# Connectors.net
KiCad netlist of a schematic drawn in Altium Designer
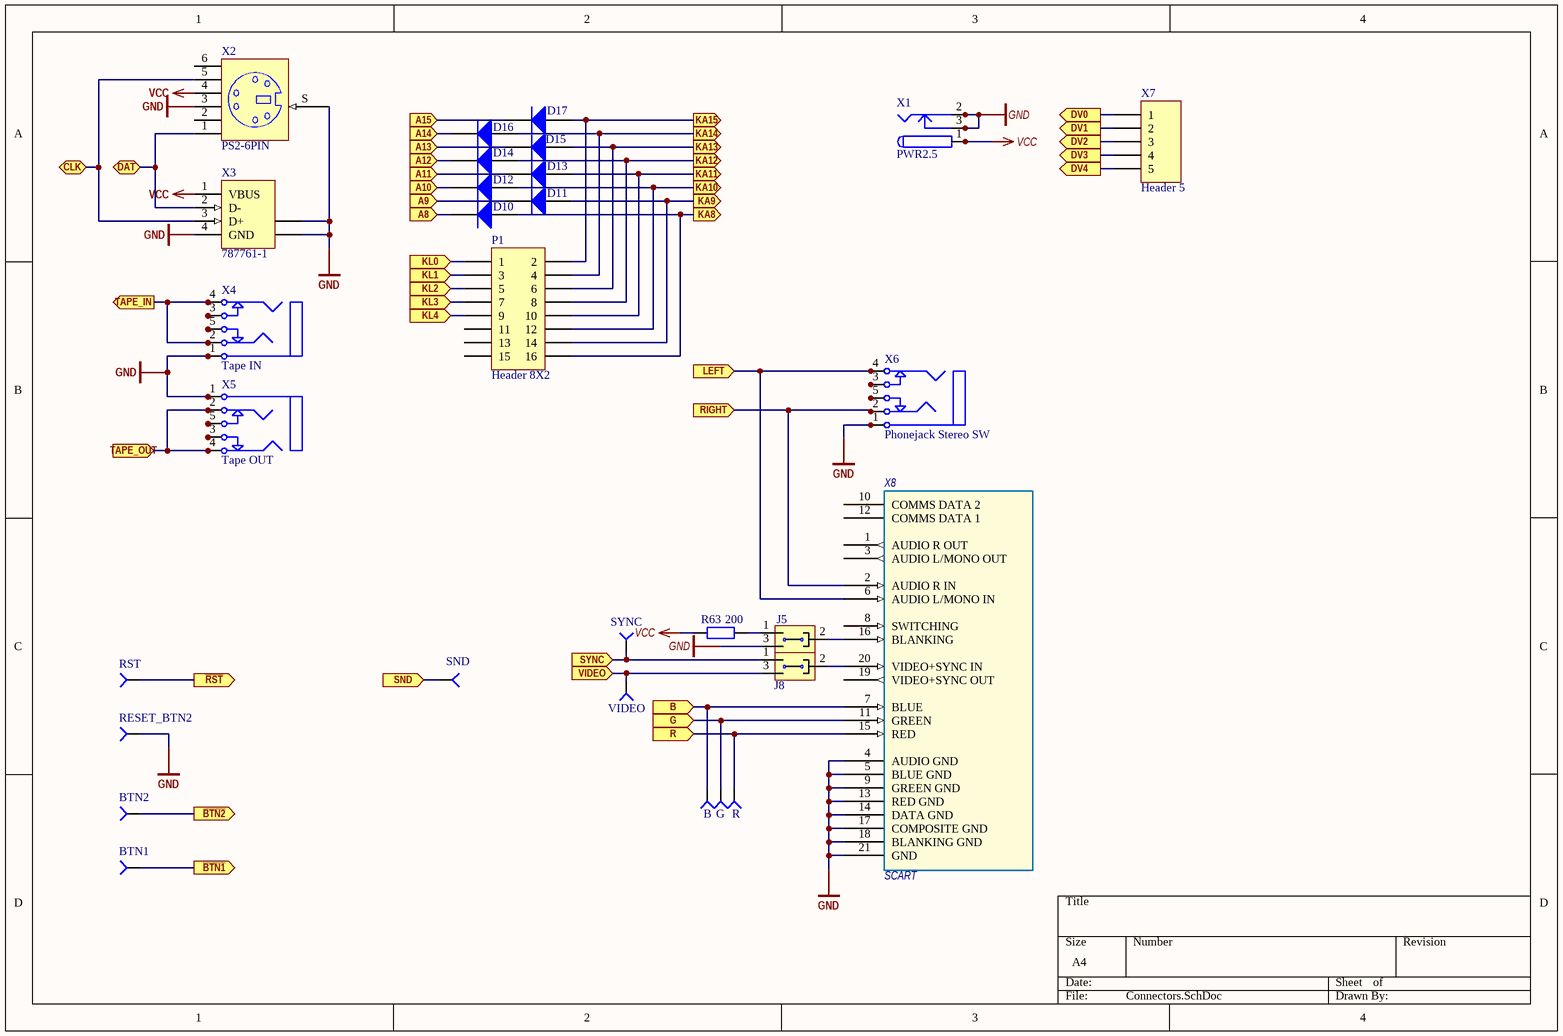
[diagram p0: Connectors.SchDoc]

(export (version "E")
  (design (tool "Eeschema 10.0.6"))
  (components
    (comp (ref "B")
      (value "~")
      (footprint "PIN1")
      (description "Socket")
      (fields (field (name "PUBLISHER") "Altium Limited"))
      (libsource (lib "Lenin") (part "Socket"))
    )
    (comp (ref "BTN1")
      (value "Socket")
      (footprint "PIN1")
      (fields (field (name "PUBLISHER") "Altium Limited"))
      (libsource (lib "Lenin") (part "Socket"))
    )
    (comp (ref "BTN2")
      (value "Socket")
      (footprint "PIN1")
      (fields (field (name "PUBLISHER") "Altium Limited"))
      (libsource (lib "Lenin") (part "Socket"))
    )
    (comp (ref "D10")
      (value "Diode 1N4148")
      (footprint "DO-35")
      (description "High Conductance Fast Diode")
      (fields (field (name "PUBLISHER") "Altium Limited"))
      (libsource (lib "Miscellaneous Devices") (part "Diode 1N4148"))
    )
    (comp (ref "D11")
      (value "Diode 1N4148")
      (footprint "DO-35")
      (description "High Conductance Fast Diode")
      (fields (field (name "PUBLISHER") "Altium Limited"))
      (libsource (lib "Miscellaneous Devices") (part "Diode 1N4148"))
    )
    (comp (ref "D12")
      (value "Diode 1N4148")
      (footprint "DO-35")
      (description "High Conductance Fast Diode")
      (fields (field (name "PUBLISHER") "Altium Limited"))
      (libsource (lib "Miscellaneous Devices") (part "Diode 1N4148"))
    )
    (comp (ref "D13")
      (value "Diode 1N4148")
      (footprint "DO-35")
      (description "High Conductance Fast Diode")
      (fields (field (name "PUBLISHER") "Altium Limited"))
      (libsource (lib "Miscellaneous Devices") (part "Diode 1N4148"))
    )
    (comp (ref "D14")
      (value "Diode 1N4148")
      (footprint "DO-35")
      (description "High Conductance Fast Diode")
      (fields (field (name "PUBLISHER") "Altium Limited"))
      (libsource (lib "Miscellaneous Devices") (part "Diode 1N4148"))
    )
    (comp (ref "D15")
      (value "Diode 1N4148")
      (footprint "DO-35")
      (description "High Conductance Fast Diode")
      (fields (field (name "PUBLISHER") "Altium Limited"))
      (libsource (lib "Miscellaneous Devices") (part "Diode 1N4148"))
    )
    (comp (ref "D16")
      (value "Diode 1N4148")
      (footprint "DO-35")
      (description "High Conductance Fast Diode")
      (fields (field (name "PUBLISHER") "Altium Limited"))
      (libsource (lib "Miscellaneous Devices") (part "Diode 1N4148"))
    )
    (comp (ref "D17")
      (value "Diode 1N4148")
      (footprint "DO-35")
      (description "High Conductance Fast Diode")
      (fields (field (name "PUBLISHER") "Altium Limited"))
      (libsource (lib "Miscellaneous Devices") (part "Diode 1N4148"))
    )
    (comp (ref "G")
      (value "~")
      (footprint "PIN1")
      (description "Socket")
      (fields (field (name "PUBLISHER") "Altium Limited"))
      (libsource (lib "Lenin") (part "Socket"))
    )
    (comp (ref "J5")
      (value "Jump3")
      (footprint "Miscellaneous Connectors:MHDR1X3")
      (libsource (lib "Lenin") (part "Jump3"))
    )
    (comp (ref "J8")
      (value "Jump3")
      (footprint "Miscellaneous Connectors:MHDR1X3")
      (libsource (lib "Lenin") (part "Jump3"))
    )
    (comp (ref "P1")
      (value "Header 8X2")
      (footprint "HDR2X8")
      (description "Header, 8-Pin, Dual row")
      (fields (field (name "PUBLISHER") "Altium Limited"))
      (libsource (lib "Miscellaneous Connectors") (part "Header 8X2"))
    )
    (comp (ref "R")
      (value "~")
      (footprint "PIN1")
      (description "Socket")
      (fields (field (name "PUBLISHER") "Altium Limited"))
      (libsource (lib "Lenin") (part "Socket"))
    )
    (comp (ref "R63")
      (value "200")
      (footprint "Lenin:AXIAL-0.4")
      (description "Resistor")
      (fields (field (name "Comment") "Res2") (field (name "PUBLISHER") "Altium Limited"))
      (libsource (lib "Lenin") (part "Res2"))
    )
    (comp (ref "RESET_BTN2")
      (value "~")
      (footprint "PIN1")
      (description "Socket")
      (fields (field (name "PUBLISHER") "Altium Limited"))
      (libsource (lib "Lenin") (part "Socket"))
    )
    (comp (ref "RST")
      (value "~")
      (footprint "PIN1")
      (description "Socket")
      (fields (field (name "PUBLISHER") "Altium Limited"))
      (libsource (lib "Lenin") (part "Socket"))
    )
    (comp (ref "SND")
      (value "~")
      (footprint "PIN1")
      (description "Socket")
      (fields (field (name "PUBLISHER") "Altium Limited"))
      (libsource (lib "Lenin") (part "Socket"))
    )
    (comp (ref "SYNC")
      (value "~")
      (footprint "PIN1")
      (description "Socket")
      (fields (field (name "PUBLISHER") "Altium Limited"))
      (libsource (lib "Lenin") (part "Socket"))
    )
    (comp (ref "VIDEO")
      (value "~")
      (footprint "PIN1")
      (description "Socket")
      (fields (field (name "PUBLISHER") "Altium Limited"))
      (libsource (lib "Lenin") (part "Socket"))
    )
    (comp (ref "X1")
      (value "PWR2.5")
      (footprint "KLD-0202")
      (description "Low Voltage Power Supply Connector")
      (fields (field (name "PUBLISHER") "Altium Limited"))
      (libsource (lib "Miscellaneous Connectors") (part "PWR2.5"))
    )
    (comp (ref "X2")
      (value "PS2-6PIN")
      (footprint "PS2-6PIN")
      (description "6 Pin Through Hole PS2 Socket (Kycon P/N)")
      (fields (field (name "PUBLISHER") "Altium Limited"))
      (libsource (lib "Miscellaneous Connectors") (part "PS2-6PIN"))
    )
    (comp (ref "X3")
      (value "787761-1")
      (footprint "787761")
      (description "USB 1.1, Right Angle, Thru-Hole, A Type, Receptacle, 4 Position, Black")
      (fields (field (name "PUBLISHER") "Altium Limited"))
      (libsource (lib "AMP Serial Bus USB") (part "787761-1"))
    )
    (comp (ref "X4")
      (value "Tape IN")
      (footprint "ST-3150-5N")
      (description "3-Conductor Jack with 2 break contacts (normals) and 2 auxiliary make contacts")
      (fields (field (name "PUBLISHER") "Altium Limited"))
      (libsource (lib "Miscellaneous Connectors") (part "Phonejack Stereo SW"))
    )
    (comp (ref "X5")
      (value "Tape OUT")
      (footprint "ST-3150-5N")
      (description "3-Conductor Jack with 2 break contacts (normals) and 2 auxiliary make contacts")
      (fields (field (name "PUBLISHER") "Altium Limited"))
      (libsource (lib "Miscellaneous Connectors") (part "Phonejack Stereo SW"))
    )
    (comp (ref "X6")
      (value "Phonejack Stereo SW")
      (footprint "ST-3150-5N")
      (description "3-Conductor Jack with 2 break contacts (normals) and 2 auxiliary make contacts")
      (fields (field (name "PUBLISHER") "Altium Limited"))
      (libsource (lib "Miscellaneous Connectors") (part "Phonejack Stereo SW"))
    )
    (comp (ref "X7")
      (value "Header 5")
      (footprint "HDR1X5")
      (description "Header, 5-Pin")
      (fields (field (name "PUBLISHER") "Altium Limited"))
      (libsource (lib "Miscellaneous Connectors") (part "Header 5"))
    )
    (comp (ref "X8") (value "SCART") (footprint "Lenin:SCART") (libsource (lib "Lenin") (part "SCART")))
  )
  (nets
    (net (code "1") (name "/A8") (class "Default")
      (node (ref "D10") (pin "2") (pinfunction "K_2") (pintype "passive"))
    )
    (net (code "2") (name "/A9") (class "Default")
      (node (ref "D11") (pin "2") (pinfunction "K_2") (pintype "passive"))
    )
    (net (code "3") (name "/A10") (class "Default")
      (node (ref "D12") (pin "2") (pinfunction "K_2") (pintype "passive"))
    )
    (net (code "4") (name "/A11") (class "Default")
      (node (ref "D13") (pin "2") (pinfunction "K_2") (pintype "passive"))
    )
    (net (code "5") (name "/A12") (class "Default")
      (node (ref "D14") (pin "2") (pinfunction "K_2") (pintype "passive"))
    )
    (net (code "6") (name "/A13") (class "Default")
      (node (ref "D15") (pin "2") (pinfunction "K_2") (pintype "passive"))
    )
    (net (code "7") (name "/A14") (class "Default")
      (node (ref "D16") (pin "2") (pinfunction "K_2") (pintype "passive"))
    )
    (net (code "8") (name "/A15") (class "Default")
      (node (ref "D17") (pin "2") (pinfunction "K_2") (pintype "passive"))
    )
    (net (code "9") (name "/B") (class "Default")
      (node (ref "B") (pin "1") (pinfunction "1_1") (pintype "passive"))
      (node (ref "X8") (pin "7") (pinfunction "BLUE_7") (pintype "input"))
    )
    (net (code "10") (name "/CLK") (class "Default")
      (node (ref "X2") (pin "5") (pinfunction "5_5") (pintype "passive"))
      (node (ref "X3") (pin "3") (pinfunction "D+_3") (pintype "input"))
    )
    (net (code "11") (name "/DAT") (class "Default")
      (node (ref "X2") (pin "1") (pinfunction "1_1") (pintype "passive"))
      (node (ref "X3") (pin "2") (pinfunction "D-_2") (pintype "input"))
    )
    (net (code "12") (name "/DV0") (class "Default")
      (node (ref "X7") (pin "1") (pinfunction "1_1") (pintype "passive"))
    )
    (net (code "13") (name "/DV1") (class "Default")
      (node (ref "X7") (pin "2") (pinfunction "2_2") (pintype "passive"))
    )
    (net (code "14") (name "/DV2") (class "Default")
      (node (ref "X7") (pin "3") (pinfunction "3_3") (pintype "passive"))
    )
    (net (code "15") (name "/DV3") (class "Default")
      (node (ref "X7") (pin "4") (pinfunction "4_4") (pintype "passive"))
    )
    (net (code "16") (name "/DV4") (class "Default")
      (node (ref "X7") (pin "5") (pinfunction "5_5") (pintype "passive"))
    )
    (net (code "17") (name "/G") (class "Default")
      (node (ref "G") (pin "1") (pinfunction "1_1") (pintype "passive"))
      (node (ref "X8") (pin "11") (pinfunction "GREEN_11") (pintype "input"))
    )
    (net (code "18") (name "/KA8") (class "Default")
      (node (ref "D10") (pin "1") (pinfunction "A_1") (pintype "passive"))
      (node (ref "P1") (pin "16") (pinfunction "16_16") (pintype "passive"))
    )
    (net (code "19") (name "/KA9") (class "Default")
      (node (ref "D11") (pin "1") (pinfunction "A_1") (pintype "passive"))
      (node (ref "P1") (pin "14") (pinfunction "14_14") (pintype "passive"))
    )
    (net (code "20") (name "/KA10") (class "Default")
      (node (ref "D12") (pin "1") (pinfunction "A_1") (pintype "passive"))
      (node (ref "P1") (pin "12") (pinfunction "12_12") (pintype "passive"))
    )
    (net (code "21") (name "/KA11") (class "Default")
      (node (ref "D13") (pin "1") (pinfunction "A_1") (pintype "passive"))
      (node (ref "P1") (pin "10") (pinfunction "10_10") (pintype "passive"))
    )
    (net (code "22") (name "/KA12") (class "Default")
      (node (ref "D14") (pin "1") (pinfunction "A_1") (pintype "passive"))
      (node (ref "P1") (pin "8") (pinfunction "8_8") (pintype "passive"))
    )
    (net (code "23") (name "/KA13") (class "Default")
      (node (ref "D15") (pin "1") (pinfunction "A_1") (pintype "passive"))
      (node (ref "P1") (pin "6") (pinfunction "6_6") (pintype "passive"))
    )
    (net (code "24") (name "/KA14") (class "Default")
      (node (ref "D16") (pin "1") (pinfunction "A_1") (pintype "passive"))
      (node (ref "P1") (pin "4") (pinfunction "4_4") (pintype "passive"))
    )
    (net (code "25") (name "/KA15") (class "Default")
      (node (ref "D17") (pin "1") (pinfunction "A_1") (pintype "passive"))
      (node (ref "P1") (pin "2") (pinfunction "2_2") (pintype "passive"))
    )
    (net (code "26") (name "/KL0") (class "Default")
      (node (ref "P1") (pin "1") (pinfunction "1_1") (pintype "passive"))
    )
    (net (code "27") (name "/KL1") (class "Default")
      (node (ref "P1") (pin "3") (pinfunction "3_3") (pintype "passive"))
    )
    (net (code "28") (name "/KL2") (class "Default")
      (node (ref "P1") (pin "5") (pinfunction "5_5") (pintype "passive"))
    )
    (net (code "29") (name "/KL3") (class "Default")
      (node (ref "P1") (pin "7") (pinfunction "7_7") (pintype "passive"))
    )
    (net (code "30") (name "/KL4") (class "Default")
      (node (ref "P1") (pin "9") (pinfunction "9_9") (pintype "passive"))
    )
    (net (code "31") (name "/LEFT") (class "Default")
      (node (ref "X6") (pin "4") (pinfunction "4_4") (pintype "passive"))
      (node (ref "X6") (pin "4A") (pinfunction "4A_4A") (pintype "passive"))
      (node (ref "X6") (pin "4B") (pinfunction "4B_4B") (pintype "passive"))
      (node (ref "X8") (pin "6") (pinfunction "AUDIO_L/MONO_IN_6") (pintype "input"))
    )
    (net (code "32") (name "/R") (class "Default")
      (node (ref "R") (pin "1") (pinfunction "1_1") (pintype "passive"))
      (node (ref "X8") (pin "15") (pinfunction "RED_15") (pintype "input"))
    )
    (net (code "33") (name "/RIGHT") (class "Default")
      (node (ref "X6") (pin "2") (pinfunction "2_2") (pintype "passive"))
      (node (ref "X6") (pin "2A") (pinfunction "2A_2A") (pintype "passive"))
      (node (ref "X6") (pin "2B") (pinfunction "2B_2B") (pintype "passive"))
      (node (ref "X8") (pin "2") (pinfunction "AUDIO_R_IN_2") (pintype "input"))
    )
    (net (code "34") (name "/SND") (class "Default")
      (node (ref "SND") (pin "1") (pinfunction "1_1") (pintype "passive"))
    )
    (net (code "35") (name "/SYNC") (class "Default")
      (node (ref "J8") (pin "1") (pintype "passive"))
      (node (ref "SYNC") (pin "1") (pinfunction "1_1") (pintype "passive"))
    )
    (net (code "36") (name "/TAPE_IN") (class "Default")
      (node (ref "X4") (pin "2") (pinfunction "2_2") (pintype "passive"))
      (node (ref "X4") (pin "2A") (pinfunction "2A_2A") (pintype "passive"))
      (node (ref "X4") (pin "2B") (pinfunction "2B_2B") (pintype "passive"))
      (node (ref "X4") (pin "4") (pinfunction "4_4") (pintype "passive"))
      (node (ref "X4") (pin "4A") (pinfunction "4A_4A") (pintype "passive"))
      (node (ref "X4") (pin "4B") (pinfunction "4B_4B") (pintype "passive"))
    )
    (net (code "37") (name "/TAPE_OUT") (class "Default")
      (node (ref "X5") (pin "2") (pinfunction "2_2") (pintype "passive"))
      (node (ref "X5") (pin "2A") (pinfunction "2A_2A") (pintype "passive"))
      (node (ref "X5") (pin "2B") (pinfunction "2B_2B") (pintype "passive"))
      (node (ref "X5") (pin "4") (pinfunction "4_4") (pintype "passive"))
      (node (ref "X5") (pin "4A") (pinfunction "4A_4A") (pintype "passive"))
      (node (ref "X5") (pin "4B") (pinfunction "4B_4B") (pintype "passive"))
    )
    (net (code "38") (name "/VIDEO") (class "Default")
      (node (ref "J8") (pin "3") (pintype "passive"))
      (node (ref "VIDEO") (pin "1") (pinfunction "1_1") (pintype "passive"))
    )
    (net (code "39") (name "/~{BTN1}") (class "Default")
      (node (ref "BTN1") (pin "1") (pinfunction "1_1") (pintype "passive"))
    )
    (net (code "40") (name "/~{BTN2}") (class "Default")
      (node (ref "BTN2") (pin "1") (pinfunction "1_1") (pintype "passive"))
    )
    (net (code "41") (name "/~{RST}") (class "Default")
      (node (ref "RST") (pin "1") (pinfunction "1_1") (pintype "passive"))
    )
    (net (code "42") (name "GND") (class "Default")
      (node (ref "J5") (pin "3") (pintype "passive"))
      (node (ref "RESET_BTN2") (pin "1") (pinfunction "1_1") (pintype "passive"))
      (node (ref "X1") (pin "2") (pinfunction "2_2") (pintype "power_in"))
      (node (ref "X1") (pin "2A") (pinfunction "2A_2A") (pintype "power_in"))
      (node (ref "X1") (pin "2B") (pinfunction "2B_2B") (pintype "power_in"))
      (node (ref "X1") (pin "3") (pinfunction "3_3") (pintype "power_in"))
      (node (ref "X1") (pin "3A") (pinfunction "3A_3A") (pintype "power_in"))
      (node (ref "X1") (pin "3B") (pinfunction "3B_3B") (pintype "power_in"))
      (node (ref "X2") (pin "3") (pinfunction "3_3") (pintype "passive"))
      (node (ref "X2") (pin "S") (pinfunction "S_S") (pintype "input"))
      (node (ref "X3") (pin "4") (pinfunction "GND_4") (pintype "power_in"))
      (node (ref "X3") (pin "5") (pinfunction "SHLD_5") (pintype "passive"))
      (node (ref "X3") (pin "6") (pinfunction "SHLD_6") (pintype "passive"))
      (node (ref "X4") (pin "1") (pinfunction "1_1") (pintype "passive"))
      (node (ref "X4") (pin "1A") (pinfunction "1A_1A") (pintype "passive"))
      (node (ref "X4") (pin "1B") (pinfunction "1B_1B") (pintype "passive"))
      (node (ref "X5") (pin "1") (pinfunction "1_1") (pintype "passive"))
      (node (ref "X5") (pin "1A") (pinfunction "1A_1A") (pintype "passive"))
      (node (ref "X5") (pin "1B") (pinfunction "1B_1B") (pintype "passive"))
      (node (ref "X6") (pin "1") (pinfunction "1_1") (pintype "passive"))
      (node (ref "X6") (pin "1A") (pinfunction "1A_1A") (pintype "passive"))
      (node (ref "X6") (pin "1B") (pinfunction "1B_1B") (pintype "passive"))
      (node (ref "X8") (pin "13") (pinfunction "RED_GND_13") (pintype "power_in"))
      (node (ref "X8") (pin "14") (pinfunction "DATA_GND_14") (pintype "power_in"))
      (node (ref "X8") (pin "17") (pinfunction "COMPOSITE_GND_17") (pintype "power_in"))
      (node (ref "X8") (pin "18") (pinfunction "BLANKING_GND_18") (pintype "power_in"))
      (node (ref "X8") (pin "21") (pinfunction "GND_21") (pintype "power_in"))
      (node (ref "X8") (pin "4") (pinfunction "AUDIO_GND_4") (pintype "power_in"))
      (node (ref "X8") (pin "5") (pinfunction "BLUE_GND_5") (pintype "power_in"))
      (node (ref "X8") (pin "9") (pinfunction "GREEN_GND_9") (pintype "power_in"))
    )
    (net (code "43") (name "Net-(J5-Pad1)") (class "Default")
      (node (ref "J5") (pin "1") (pintype "passive"))
      (node (ref "R63") (pin "2") (pinfunction "2_2") (pintype "passive"))
    )
    (net (code "44") (name "Net-(X4-Pad3)") (class "Default")
      (node (ref "X4") (pin "3") (pinfunction "3_3") (pintype "passive"))
      (node (ref "X4") (pin "3A") (pinfunction "3A_3A") (pintype "passive"))
      (node (ref "X4") (pin "3B") (pinfunction "3B_3B") (pintype "passive"))
    )
    (net (code "45") (name "Net-(X4-Pad5)") (class "Default")
      (node (ref "X4") (pin "5") (pinfunction "5_5") (pintype "passive"))
      (node (ref "X4") (pin "5A") (pinfunction "5A_5A") (pintype "passive"))
      (node (ref "X4") (pin "5B") (pinfunction "5B_5B") (pintype "passive"))
    )
    (net (code "46") (name "Net-(X5-Pad3)") (class "Default")
      (node (ref "X5") (pin "3") (pinfunction "3_3") (pintype "passive"))
      (node (ref "X5") (pin "3A") (pinfunction "3A_3A") (pintype "passive"))
      (node (ref "X5") (pin "3B") (pinfunction "3B_3B") (pintype "passive"))
    )
    (net (code "47") (name "Net-(X5-Pad5)") (class "Default")
      (node (ref "X5") (pin "5") (pinfunction "5_5") (pintype "passive"))
      (node (ref "X5") (pin "5A") (pinfunction "5A_5A") (pintype "passive"))
      (node (ref "X5") (pin "5B") (pinfunction "5B_5B") (pintype "passive"))
    )
    (net (code "48") (name "Net-(X6-Pad3)") (class "Default")
      (node (ref "X6") (pin "3") (pinfunction "3_3") (pintype "passive"))
      (node (ref "X6") (pin "3A") (pinfunction "3A_3A") (pintype "passive"))
      (node (ref "X6") (pin "3B") (pinfunction "3B_3B") (pintype "passive"))
    )
    (net (code "49") (name "Net-(X6-Pad5)") (class "Default")
      (node (ref "X6") (pin "5") (pinfunction "5_5") (pintype "passive"))
      (node (ref "X6") (pin "5A") (pinfunction "5A_5A") (pintype "passive"))
      (node (ref "X6") (pin "5B") (pinfunction "5B_5B") (pintype "passive"))
    )
    (net (code "50") (name "Net-(X8-BLANKING)") (class "Default")
      (node (ref "J5") (pin "2") (pintype "passive"))
      (node (ref "X8") (pin "16") (pinfunction "BLANKING_16") (pintype "input"))
    )
    (net (code "51") (name "Net-(X8-VIDEO+SYNC_IN)") (class "Default")
      (node (ref "J8") (pin "2") (pintype "passive"))
      (node (ref "X8") (pin "20") (pinfunction "VIDEO+SYNC_IN_20") (pintype "input"))
    )
    (net (code "52") (name "VCC") (class "Default")
      (node (ref "R63") (pin "1") (pinfunction "1_1") (pintype "passive"))
      (node (ref "X1") (pin "1") (pinfunction "1_1") (pintype "power_in"))
      (node (ref "X1") (pin "1A") (pinfunction "1A_1A") (pintype "power_in"))
      (node (ref "X1") (pin "1B") (pinfunction "1B_1B") (pintype "power_in"))
      (node (ref "X2") (pin "4") (pinfunction "4_4") (pintype "passive"))
      (node (ref "X3") (pin "1") (pinfunction "VBUS_1") (pintype "power_in"))
    )
    (net (code "53") (name "unconnected-(P1-Pad11)") (class "Default")
      (node (ref "P1") (pin "11") (pinfunction "11_11") (pintype "passive"))
    )
    (net (code "54") (name "unconnected-(P1-Pad13)") (class "Default")
      (node (ref "P1") (pin "13") (pinfunction "13_13") (pintype "passive"))
    )
    (net (code "55") (name "unconnected-(P1-Pad15)") (class "Default")
      (node (ref "P1") (pin "15") (pinfunction "15_15") (pintype "passive"))
    )
    (net (code "56") (name "unconnected-(X2-Pad2)") (class "Default")
      (node (ref "X2") (pin "2") (pinfunction "2_2") (pintype "passive"))
    )
    (net (code "57") (name "unconnected-(X2-Pad6)") (class "Default")
      (node (ref "X2") (pin "6") (pinfunction "6_6") (pintype "passive"))
    )
    (net (code "58") (name "unconnected-(X8-AUDIO_L{slash}MONO_OUT-Pad3)") (class "Default")
      (node (ref "X8") (pin "3") (pinfunction "AUDIO_L/MONO_OUT_3") (pintype "output"))
    )
    (net (code "59") (name "unconnected-(X8-AUDIO_R_OUT-Pad1)") (class "Default")
      (node (ref "X8") (pin "1") (pinfunction "AUDIO_R_OUT_1") (pintype "output"))
    )
    (net (code "60") (name "unconnected-(X8-COMMS_DATA_1-Pad12)") (class "Default")
      (node (ref "X8") (pin "12") (pinfunction "COMMS_DATA_1_12") (pintype "passive"))
    )
    (net (code "61") (name "unconnected-(X8-COMMS_DATA_2-Pad10)") (class "Default")
      (node (ref "X8") (pin "10") (pinfunction "COMMS_DATA_2_10") (pintype "passive"))
    )
    (net (code "62") (name "unconnected-(X8-SWITCHING-Pad8)") (class "Default")
      (node (ref "X8") (pin "8") (pinfunction "SWITCHING_8") (pintype "input"))
    )
    (net (code "63") (name "unconnected-(X8-VIDEO+SYNC_OUT-Pad19)") (class "Default")
      (node (ref "X8") (pin "19") (pinfunction "VIDEO+SYNC_OUT_19") (pintype "output"))
    )
  )
)
